# uwbreceiver.net
KiCad netlist of a schematic drawn in EAGLE
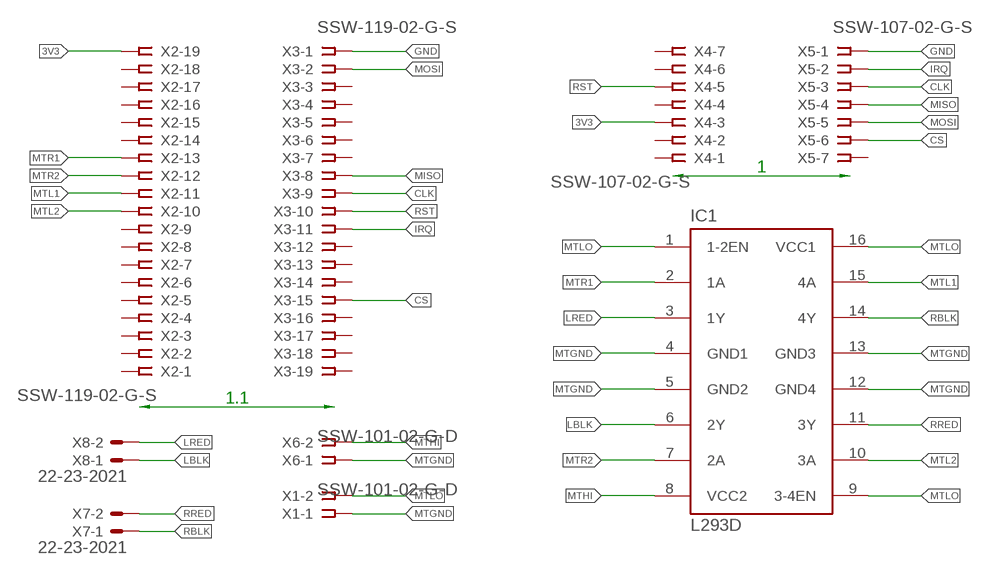
[diagram p0: schematic, sheet 1]

(export (version "E")
  (design (tool "Eeschema 10.0.6"))
  (components
    (comp (ref "IC1")
      (value "L293D")
      (footprint "eagle-import:DIL16")
      (libsource (lib "eagle-import") (part "L293D"))
    )
    (comp (ref "X1")
      (value "SSW-101-02-G-D")
      (footprint "eagle-import:SSW-101-02-G-D")
      (fields (field (name "MF") "Samtec Inc."))
      (libsource (lib "eagle-import") (part "SSW-101-02-G-D"))
    )
    (comp (ref "X2")
      (value "SSW-119-02-G-S")
      (footprint "eagle-import:SSW-119-02-G-S")
      (fields (field (name "MF") "Samtec Inc."))
      (libsource (lib "eagle-import") (part "SSW-119-02-G-S"))
    )
    (comp (ref "X3")
      (value "SSW-119-02-G-S")
      (footprint "eagle-import:SSW-119-02-G-S")
      (fields (field (name "MF") "Samtec Inc."))
      (libsource (lib "eagle-import") (part "SSW-119-02-G-S"))
    )
    (comp (ref "X4")
      (value "SSW-107-02-G-S")
      (footprint "eagle-import:SSW-107-02-G-S")
      (fields (field (name "MF") "Samtec Inc."))
      (libsource (lib "eagle-import") (part "SSW-107-02-G-S"))
    )
    (comp (ref "X5")
      (value "SSW-107-02-G-S")
      (footprint "eagle-import:SSW-107-02-G-S")
      (fields (field (name "MF") "Samtec Inc."))
      (libsource (lib "eagle-import") (part "SSW-107-02-G-S"))
    )
    (comp (ref "X6")
      (value "SSW-101-02-G-D")
      (footprint "eagle-import:SSW-101-02-G-D")
      (fields (field (name "MF") "Samtec Inc."))
      (libsource (lib "eagle-import") (part "SSW-101-02-G-D"))
    )
    (comp (ref "X7")
      (value "22-23-2021")
      (footprint "eagle-import:22-23-2021")
      (fields (field (name "MF") "MOLEX"))
      (libsource (lib "eagle-import") (part "22-23-2021"))
    )
    (comp (ref "X8")
      (value "22-23-2021")
      (footprint "eagle-import:22-23-2021")
      (fields (field (name "MF") "MOLEX"))
      (libsource (lib "eagle-import") (part "22-23-2021"))
    )
  )
  (nets
    (net (code "1") (name "3V3") (class "Default")
      (node (ref "X2") (pin "19") (pinfunction "1_19") (pintype "passive"))
      (node (ref "X4") (pin "3") (pinfunction "1_3") (pintype "passive"))
    )
    (net (code "2") (name "CLK") (class "Default")
      (node (ref "X3") (pin "9") (pinfunction "1_9") (pintype "passive"))
      (node (ref "X5") (pin "3") (pinfunction "1_3") (pintype "passive"))
    )
    (net (code "3") (name "CS") (class "Default")
      (node (ref "X3") (pin "15") (pinfunction "1_15") (pintype "passive"))
      (node (ref "X5") (pin "6") (pinfunction "1_6") (pintype "passive"))
    )
    (net (code "4") (name "GND") (class "Default")
      (node (ref "X3") (pin "1") (pinfunction "1_1") (pintype "passive"))
      (node (ref "X5") (pin "1") (pinfunction "1_1") (pintype "passive"))
    )
    (net (code "5") (name "IRQ") (class "Default")
      (node (ref "X3") (pin "11") (pinfunction "1_11") (pintype "passive"))
      (node (ref "X5") (pin "2") (pinfunction "1_2") (pintype "passive"))
    )
    (net (code "6") (name "LBLK") (class "Default")
      (node (ref "IC1") (pin "6") (pinfunction "2Y_6") (pintype "output"))
      (node (ref "X8") (pin "1") (pinfunction "S_1") (pintype "passive"))
    )
    (net (code "7") (name "LRED") (class "Default")
      (node (ref "IC1") (pin "3") (pinfunction "1Y_3") (pintype "output"))
      (node (ref "X8") (pin "2") (pinfunction "S_2") (pintype "passive"))
    )
    (net (code "8") (name "MISO") (class "Default")
      (node (ref "X3") (pin "8") (pinfunction "1_8") (pintype "passive"))
      (node (ref "X5") (pin "4") (pinfunction "1_4") (pintype "passive"))
    )
    (net (code "9") (name "MOSI") (class "Default")
      (node (ref "X3") (pin "2") (pinfunction "1_2") (pintype "passive"))
      (node (ref "X5") (pin "5") (pinfunction "1_5") (pintype "passive"))
    )
    (net (code "10") (name "MTGND") (class "Default")
      (node (ref "IC1") (pin "12") (pinfunction "GND4_12") (pintype "power_in"))
      (node (ref "IC1") (pin "13") (pinfunction "GND3_13") (pintype "power_in"))
      (node (ref "IC1") (pin "4") (pinfunction "GND1_4") (pintype "power_in"))
      (node (ref "IC1") (pin "5") (pinfunction "GND2_5") (pintype "power_in"))
      (node (ref "X1") (pin "1") (pinfunction "1_1") (pintype "passive"))
      (node (ref "X6") (pin "1") (pinfunction "1_1") (pintype "passive"))
    )
    (net (code "11") (name "MTHI") (class "Default")
      (node (ref "IC1") (pin "8") (pinfunction "VCC2_8") (pintype "power_in"))
      (node (ref "X6") (pin "2") (pinfunction "1_2") (pintype "passive"))
    )
    (net (code "12") (name "MTL1") (class "Default")
      (node (ref "IC1") (pin "15") (pinfunction "4A_15") (pintype "input"))
      (node (ref "X2") (pin "11") (pinfunction "1_11") (pintype "passive"))
    )
    (net (code "13") (name "MTL2") (class "Default")
      (node (ref "IC1") (pin "10") (pinfunction "3A_10") (pintype "input"))
      (node (ref "X2") (pin "10") (pinfunction "1_10") (pintype "passive"))
    )
    (net (code "14") (name "MTLO") (class "Default")
      (node (ref "IC1") (pin "1") (pinfunction "1-2EN_1") (pintype "input"))
      (node (ref "IC1") (pin "16") (pinfunction "VCC1_16") (pintype "power_in"))
      (node (ref "IC1") (pin "9") (pinfunction "3-4EN_9") (pintype "input"))
      (node (ref "X1") (pin "2") (pinfunction "1_2") (pintype "passive"))
    )
    (net (code "15") (name "MTR1") (class "Default")
      (node (ref "IC1") (pin "2") (pinfunction "1A_2") (pintype "input"))
      (node (ref "X2") (pin "13") (pinfunction "1_13") (pintype "passive"))
    )
    (net (code "16") (name "MTR2") (class "Default")
      (node (ref "IC1") (pin "7") (pinfunction "2A_7") (pintype "input"))
      (node (ref "X2") (pin "12") (pinfunction "1_12") (pintype "passive"))
    )
    (net (code "17") (name "RBLK") (class "Default")
      (node (ref "IC1") (pin "14") (pinfunction "4Y_14") (pintype "output"))
      (node (ref "X7") (pin "1") (pinfunction "S_1") (pintype "passive"))
    )
    (net (code "18") (name "RRED") (class "Default")
      (node (ref "IC1") (pin "11") (pinfunction "3Y_11") (pintype "output"))
      (node (ref "X7") (pin "2") (pinfunction "S_2") (pintype "passive"))
    )
    (net (code "19") (name "RST") (class "Default")
      (node (ref "X3") (pin "10") (pinfunction "1_10") (pintype "passive"))
      (node (ref "X4") (pin "5") (pinfunction "1_5") (pintype "passive"))
    )
    (net (code "20") (name "unconnected-(X2-Pad1)") (class "Default")
      (node (ref "X2") (pin "1") (pinfunction "1_1") (pintype "passive"))
    )
    (net (code "21") (name "unconnected-(X2F-1-Pad14)") (class "Default")
      (node (ref "X2") (pin "14") (pinfunction "1_14") (pintype "passive"))
    )
    (net (code "22") (name "unconnected-(X2G-1-Pad15)") (class "Default")
      (node (ref "X2") (pin "15") (pinfunction "1_15") (pintype "passive"))
    )
    (net (code "23") (name "unconnected-(X2H-1-Pad16)") (class "Default")
      (node (ref "X2") (pin "16") (pinfunction "1_16") (pintype "passive"))
    )
    (net (code "24") (name "unconnected-(X2I-1-Pad17)") (class "Default")
      (node (ref "X2") (pin "17") (pinfunction "1_17") (pintype "passive"))
    )
    (net (code "25") (name "unconnected-(X2J-1-Pad18)") (class "Default")
      (node (ref "X2") (pin "18") (pinfunction "1_18") (pintype "passive"))
    )
    (net (code "26") (name "unconnected-(X2L-1-Pad2)") (class "Default")
      (node (ref "X2") (pin "2") (pinfunction "1_2") (pintype "passive"))
    )
    (net (code "27") (name "unconnected-(X2M-1-Pad3)") (class "Default")
      (node (ref "X2") (pin "3") (pinfunction "1_3") (pintype "passive"))
    )
    (net (code "28") (name "unconnected-(X2N-1-Pad4)") (class "Default")
      (node (ref "X2") (pin "4") (pinfunction "1_4") (pintype "passive"))
    )
    (net (code "29") (name "unconnected-(X2O-1-Pad5)") (class "Default")
      (node (ref "X2") (pin "5") (pinfunction "1_5") (pintype "passive"))
    )
    (net (code "30") (name "unconnected-(X2P-1-Pad6)") (class "Default")
      (node (ref "X2") (pin "6") (pinfunction "1_6") (pintype "passive"))
    )
    (net (code "31") (name "unconnected-(X2Q-1-Pad7)") (class "Default")
      (node (ref "X2") (pin "7") (pinfunction "1_7") (pintype "passive"))
    )
    (net (code "32") (name "unconnected-(X2R-1-Pad8)") (class "Default")
      (node (ref "X2") (pin "8") (pinfunction "1_8") (pintype "passive"))
    )
    (net (code "33") (name "unconnected-(X2S-1-Pad9)") (class "Default")
      (node (ref "X2") (pin "9") (pinfunction "1_9") (pintype "passive"))
    )
    (net (code "34") (name "unconnected-(X3D-1-Pad12)") (class "Default")
      (node (ref "X3") (pin "12") (pinfunction "1_12") (pintype "passive"))
    )
    (net (code "35") (name "unconnected-(X3E-1-Pad13)") (class "Default")
      (node (ref "X3") (pin "13") (pinfunction "1_13") (pintype "passive"))
    )
    (net (code "36") (name "unconnected-(X3F-1-Pad14)") (class "Default")
      (node (ref "X3") (pin "14") (pinfunction "1_14") (pintype "passive"))
    )
    (net (code "37") (name "unconnected-(X3H-1-Pad16)") (class "Default")
      (node (ref "X3") (pin "16") (pinfunction "1_16") (pintype "passive"))
    )
    (net (code "38") (name "unconnected-(X3I-1-Pad17)") (class "Default")
      (node (ref "X3") (pin "17") (pinfunction "1_17") (pintype "passive"))
    )
    (net (code "39") (name "unconnected-(X3J-1-Pad18)") (class "Default")
      (node (ref "X3") (pin "18") (pinfunction "1_18") (pintype "passive"))
    )
    (net (code "40") (name "unconnected-(X3K-1-Pad19)") (class "Default")
      (node (ref "X3") (pin "19") (pinfunction "1_19") (pintype "passive"))
    )
    (net (code "41") (name "unconnected-(X3M-1-Pad3)") (class "Default")
      (node (ref "X3") (pin "3") (pinfunction "1_3") (pintype "passive"))
    )
    (net (code "42") (name "unconnected-(X3N-1-Pad4)") (class "Default")
      (node (ref "X3") (pin "4") (pinfunction "1_4") (pintype "passive"))
    )
    (net (code "43") (name "unconnected-(X3O-1-Pad5)") (class "Default")
      (node (ref "X3") (pin "5") (pinfunction "1_5") (pintype "passive"))
    )
    (net (code "44") (name "unconnected-(X3P-1-Pad6)") (class "Default")
      (node (ref "X3") (pin "6") (pinfunction "1_6") (pintype "passive"))
    )
    (net (code "45") (name "unconnected-(X3Q-1-Pad7)") (class "Default")
      (node (ref "X3") (pin "7") (pinfunction "1_7") (pintype "passive"))
    )
    (net (code "46") (name "unconnected-(X4-Pad1)") (class "Default")
      (node (ref "X4") (pin "1") (pinfunction "1_1") (pintype "passive"))
    )
    (net (code "47") (name "unconnected-(X4B-1-Pad2)") (class "Default")
      (node (ref "X4") (pin "2") (pinfunction "1_2") (pintype "passive"))
    )
    (net (code "48") (name "unconnected-(X4D-1-Pad4)") (class "Default")
      (node (ref "X4") (pin "4") (pinfunction "1_4") (pintype "passive"))
    )
    (net (code "49") (name "unconnected-(X4F-1-Pad6)") (class "Default")
      (node (ref "X4") (pin "6") (pinfunction "1_6") (pintype "passive"))
    )
    (net (code "50") (name "unconnected-(X4G-1-Pad7)") (class "Default")
      (node (ref "X4") (pin "7") (pinfunction "1_7") (pintype "passive"))
    )
    (net (code "51") (name "unconnected-(X5G-1-Pad7)") (class "Default")
      (node (ref "X5") (pin "7") (pinfunction "1_7") (pintype "passive"))
    )
  )
)
